# Motor_board_2_5.net
KiCad netlist of a schematic drawn in EAGLE
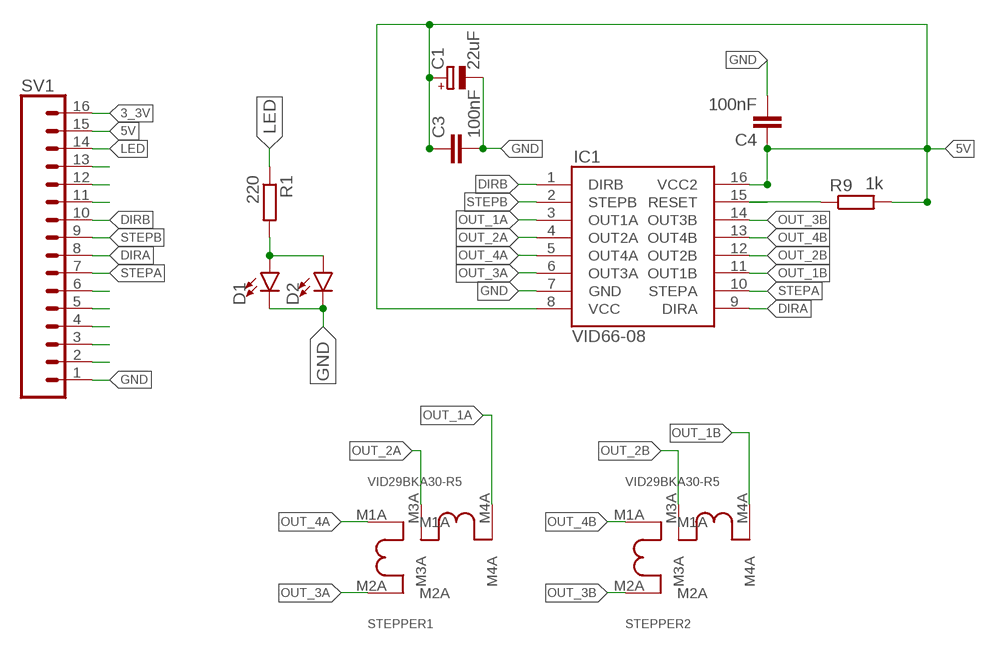
[diagram p0: schematic, sheet 1]

(export (version "E")
  (design (tool "Eeschema 10.0.6"))
  (components
    (comp (ref "C1")
      (value "22uF")
      (footprint "eagle-import:153CLV-0605")
      (libsource (lib "eagle-import") (part "CPOL-EU153CLV-0605"))
    )
    (comp (ref "C3")
      (value "100nF")
      (footprint "eagle-import:C1206K")
      (libsource (lib "eagle-import") (part "C-EUC1206K"))
    )
    (comp (ref "C4")
      (value "100nF")
      (footprint "eagle-import:C1206K")
      (libsource (lib "eagle-import") (part "C-EUC1206K"))
    )
    (comp (ref "D1")
      (value "LED-3MM-NO_SILK")
      (footprint "eagle-import:LED_3MM-NS")
      (libsource (lib "eagle-import") (part "LED-3MM-NO_SILK"))
    )
    (comp (ref "D2")
      (value "LED-3MM-NO_SILK")
      (footprint "eagle-import:LED_3MM-NS")
      (libsource (lib "eagle-import") (part "LED-3MM-NO_SILK"))
    )
    (comp (ref "IC1")
      (value "VID66-08")
      (footprint "eagle-import:SO16")
      (libsource (lib "eagle-import") (part "VID66-08"))
    )
    (comp (ref "R1")
      (value "220")
      (footprint "eagle-import:0204_7")
      (libsource (lib "eagle-import") (part "R-EU_0204/7"))
    )
    (comp (ref "R9")
      (value "1k")
      (footprint "eagle-import:M0805")
      (libsource (lib "eagle-import") (part "R-EU_M0805"))
    )
    (comp (ref "STEPPER1")
      (value "VID29BKA30-R5")
      (footprint "eagle-import:BKA30-R5")
      (libsource (lib "eagle-import") (part "VID29BKA30-R5"))
    )
    (comp (ref "STEPPER2")
      (value "VID29BKA30-R5")
      (footprint "eagle-import:BKA30-R5")
      (libsource (lib "eagle-import") (part "VID29BKA30-R5"))
    )
    (comp (ref "SV1")
      (value "CONN_16")
      (footprint "eagle-import:1X16")
      (libsource (lib "eagle-import") (part "CONN_16"))
    )
  )
  (nets
    (net (code "1") (name "3_3V") (class "Default")
      (node (ref "SV1") (pin "16") (pinfunction "16_16") (pintype "passive"))
    )
    (net (code "2") (name "5V") (class "Default")
      (node (ref "C1") (pin "+") (pinfunction "+_+") (pintype "passive"))
      (node (ref "C3") (pin "1") (pinfunction "1_1") (pintype "passive"))
      (node (ref "C4") (pin "1") (pinfunction "1_1") (pintype "passive"))
      (node (ref "IC1") (pin "16") (pinfunction "VCC2_16") (pintype "power_in"))
      (node (ref "IC1") (pin "8") (pinfunction "VCC_8") (pintype "power_in"))
      (node (ref "R9") (pin "2") (pinfunction "2_2") (pintype "passive"))
      (node (ref "SV1") (pin "15") (pinfunction "15_15") (pintype "passive"))
    )
    (net (code "3") (name "DIRA") (class "Default")
      (node (ref "IC1") (pin "9") (pinfunction "DIRA_9") (pintype "input"))
      (node (ref "SV1") (pin "8") (pinfunction "8_8") (pintype "passive"))
    )
    (net (code "4") (name "DIRB") (class "Default")
      (node (ref "IC1") (pin "1") (pinfunction "DIRB_1") (pintype "input"))
      (node (ref "SV1") (pin "10") (pinfunction "10_10") (pintype "passive"))
    )
    (net (code "5") (name "GND") (class "Default")
      (node (ref "C1") (pin "-") (pinfunction "-_-") (pintype "passive"))
      (node (ref "C3") (pin "2") (pinfunction "2_2") (pintype "passive"))
      (node (ref "C4") (pin "2") (pinfunction "2_2") (pintype "passive"))
      (node (ref "D1") (pin "K") (pinfunction "C_K") (pintype "passive"))
      (node (ref "D2") (pin "K") (pinfunction "C_K") (pintype "passive"))
      (node (ref "IC1") (pin "7") (pinfunction "GND_7") (pintype "power_in"))
      (node (ref "SV1") (pin "1") (pinfunction "1_1") (pintype "passive"))
    )
    (net (code "6") (name "LED") (class "Default")
      (node (ref "R1") (pin "1") (pinfunction "1_1") (pintype "passive"))
      (node (ref "SV1") (pin "14") (pinfunction "14_14") (pintype "passive"))
    )
    (net (code "7") (name "Net-(D1-PadA)") (class "Default")
      (node (ref "D1") (pin "A") (pinfunction "A_A") (pintype "passive"))
      (node (ref "D2") (pin "A") (pinfunction "A_A") (pintype "passive"))
      (node (ref "R1") (pin "2") (pinfunction "2_2") (pintype "passive"))
    )
    (net (code "8") (name "Net-(IC1-RESET)") (class "Default")
      (node (ref "IC1") (pin "15") (pinfunction "RESET_15") (pintype "input"))
      (node (ref "R9") (pin "1") (pinfunction "1_1") (pintype "passive"))
    )
    (net (code "9") (name "OUT_1A") (class "Default")
      (node (ref "IC1") (pin "3") (pinfunction "OUT1A_3") (pintype "output"))
      (node (ref "STEPPER1") (pin "M4A") (pinfunction "M4A_M4A") (pintype "input"))
    )
    (net (code "10") (name "OUT_1B") (class "Default")
      (node (ref "IC1") (pin "11") (pinfunction "OUT1B_11") (pintype "output"))
      (node (ref "STEPPER2") (pin "M4A") (pinfunction "M4A_M4A") (pintype "input"))
    )
    (net (code "11") (name "OUT_2A") (class "Default")
      (node (ref "IC1") (pin "4") (pinfunction "OUT2A_4") (pintype "output"))
      (node (ref "STEPPER1") (pin "M3A") (pinfunction "M3A_M3A") (pintype "input"))
    )
    (net (code "12") (name "OUT_2B") (class "Default")
      (node (ref "IC1") (pin "12") (pinfunction "OUT2B_12") (pintype "output"))
      (node (ref "STEPPER2") (pin "M3A") (pinfunction "M3A_M3A") (pintype "input"))
    )
    (net (code "13") (name "OUT_3A") (class "Default")
      (node (ref "IC1") (pin "6") (pinfunction "OUT3A_6") (pintype "output"))
      (node (ref "STEPPER1") (pin "M2A") (pinfunction "M2A_M2A") (pintype "input"))
    )
    (net (code "14") (name "OUT_3B") (class "Default")
      (node (ref "IC1") (pin "14") (pinfunction "OUT3B_14") (pintype "output"))
      (node (ref "STEPPER2") (pin "M2A") (pinfunction "M2A_M2A") (pintype "input"))
    )
    (net (code "15") (name "OUT_4A") (class "Default")
      (node (ref "IC1") (pin "5") (pinfunction "OUT4A_5") (pintype "output"))
      (node (ref "STEPPER1") (pin "M1A") (pinfunction "M1A_M1A") (pintype "input"))
    )
    (net (code "16") (name "OUT_4B") (class "Default")
      (node (ref "IC1") (pin "13") (pinfunction "OUT4B_13") (pintype "output"))
      (node (ref "STEPPER2") (pin "M1A") (pinfunction "M1A_M1A") (pintype "input"))
    )
    (net (code "17") (name "STEPA") (class "Default")
      (node (ref "IC1") (pin "10") (pinfunction "STEPA_10") (pintype "input"))
      (node (ref "SV1") (pin "7") (pinfunction "7_7") (pintype "passive"))
    )
    (net (code "18") (name "STEPB") (class "Default")
      (node (ref "IC1") (pin "2") (pinfunction "STEPB_2") (pintype "input"))
      (node (ref "SV1") (pin "9") (pinfunction "9_9") (pintype "passive"))
    )
    (net (code "19") (name "unconnected-(SV1-Pad2)") (class "Default")
      (node (ref "SV1") (pin "2") (pinfunction "2_2") (pintype "passive"))
    )
    (net (code "20") (name "unconnected-(SV1-Pad3)") (class "Default")
      (node (ref "SV1") (pin "3") (pinfunction "3_3") (pintype "passive"))
    )
    (net (code "21") (name "unconnected-(SV1-Pad4)") (class "Default")
      (node (ref "SV1") (pin "4") (pinfunction "4_4") (pintype "passive"))
    )
    (net (code "22") (name "unconnected-(SV1-Pad5)") (class "Default")
      (node (ref "SV1") (pin "5") (pinfunction "5_5") (pintype "passive"))
    )
    (net (code "23") (name "unconnected-(SV1-Pad6)") (class "Default")
      (node (ref "SV1") (pin "6") (pinfunction "6_6") (pintype "passive"))
    )
    (net (code "24") (name "unconnected-(SV1-Pad11)") (class "Default")
      (node (ref "SV1") (pin "11") (pinfunction "11_11") (pintype "passive"))
    )
    (net (code "25") (name "unconnected-(SV1-Pad12)") (class "Default")
      (node (ref "SV1") (pin "12") (pinfunction "12_12") (pintype "passive"))
    )
    (net (code "26") (name "unconnected-(SV1-Pad13)") (class "Default")
      (node (ref "SV1") (pin "13") (pinfunction "13_13") (pintype "passive"))
    )
  )
)
